# module.net
KiCad netlist of a schematic drawn in EAGLE
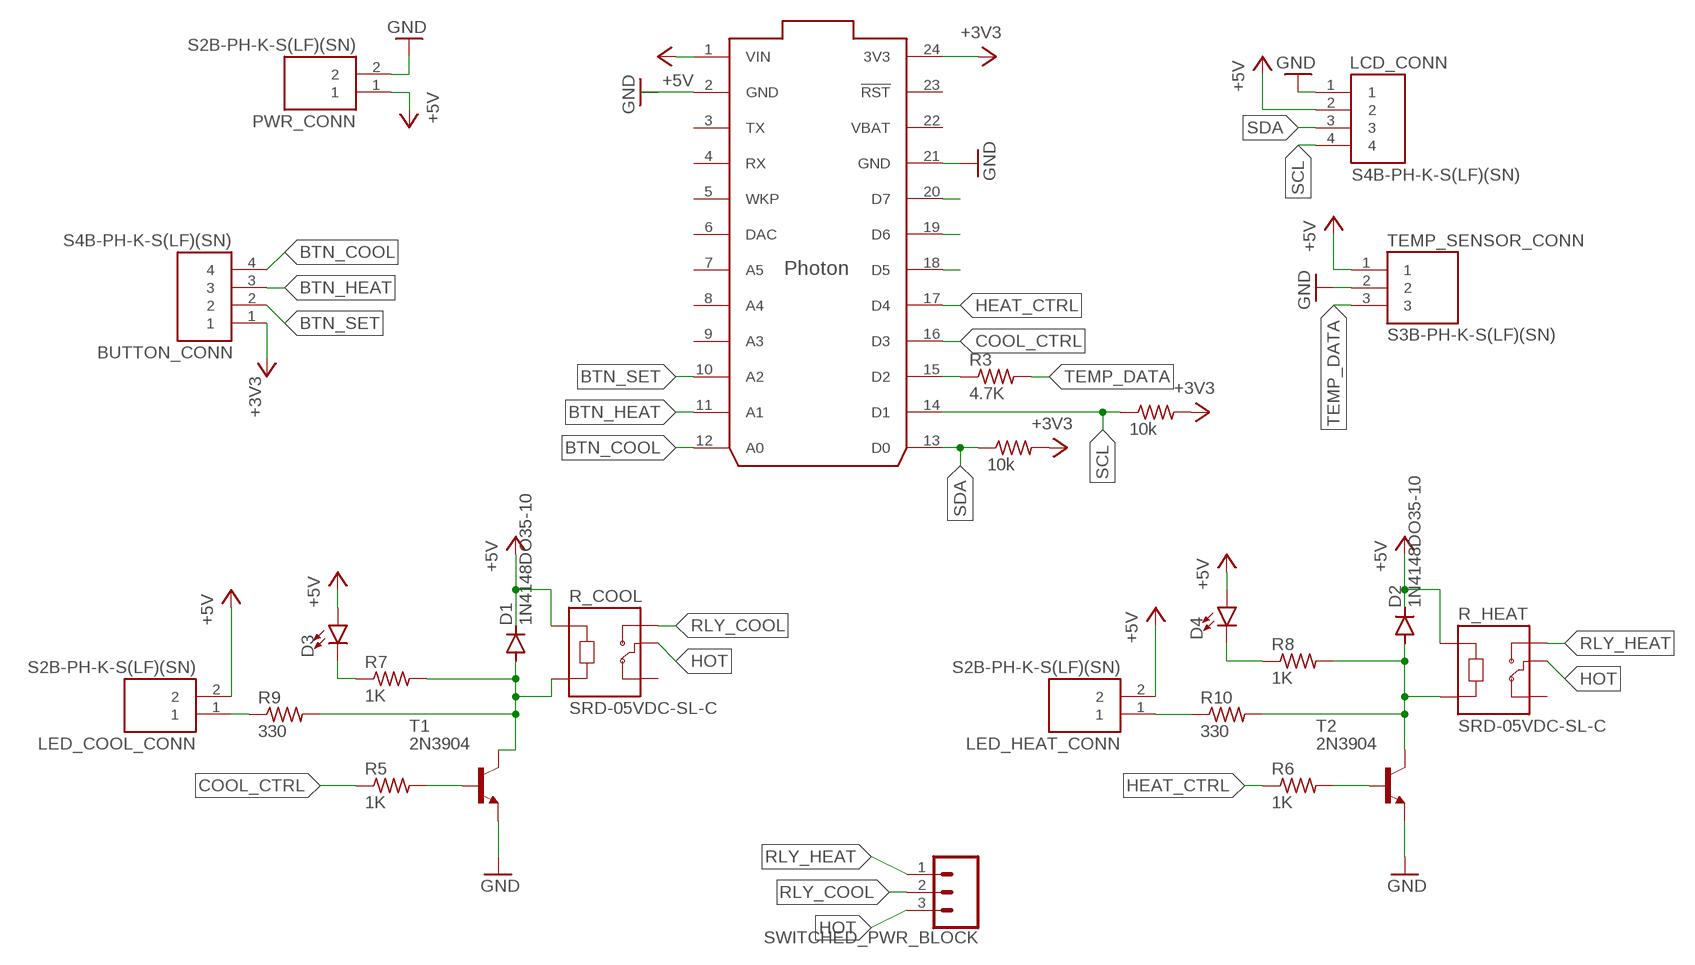
[diagram p0: schematic, sheet 1]

(export (version "E")
  (design (tool "Eeschema 10.0.6"))
  (components
    (comp (ref "BUTTON_CONN")
      (value "S4B-PH-K-S(LF)(SN)")
      (footprint "eagle-import:JST_S4B-PH-K-S(LF)(SN)")
      (fields (field (name "MF") "JST Sales"))
      (libsource (lib "eagle-import") (part "S4B-PH-K-S(LF)(SN)"))
    )
    (comp (ref "D1")
      (value "1N4148DO35-10")
      (footprint "eagle-import:DO35-10")
      (libsource (lib "eagle-import") (part "1N4148DO35-10"))
    )
    (comp (ref "D2")
      (value "1N4148DO35-10")
      (footprint "eagle-import:DO35-10")
      (libsource (lib "eagle-import") (part "1N4148DO35-10"))
    )
    (comp (ref "D3")
      (value "LED5MM")
      (footprint "eagle-import:LED_5MM")
      (libsource (lib "eagle-import") (part "LED5MM"))
    )
    (comp (ref "D4")
      (value "LED5MM")
      (footprint "eagle-import:LED_5MM")
      (libsource (lib "eagle-import") (part "LED5MM"))
    )
    (comp (ref "LCD_CONN")
      (value "S4B-PH-K-S(LF)(SN)")
      (footprint "eagle-import:JST_S4B-PH-K-S(LF)(SN)")
      (fields (field (name "MF") "JST Sales"))
      (libsource (lib "eagle-import") (part "S4B-PH-K-S(LF)(SN)"))
    )
    (comp (ref "LED_COOL_CONN")
      (value "S2B-PH-K-S(LF)(SN)")
      (footprint "eagle-import:JST_S2B-PH-K-S(LF)(SN)")
      (fields (field (name "MF") "JST Sales America Inc."))
      (libsource (lib "eagle-import") (part "S2B-PH-K-S(LF)(SN)"))
    )
    (comp (ref "LED_HEAT_CONN")
      (value "S2B-PH-K-S(LF)(SN)")
      (footprint "eagle-import:JST_S2B-PH-K-S(LF)(SN)")
      (fields (field (name "MF") "JST Sales America Inc."))
      (libsource (lib "eagle-import") (part "S2B-PH-K-S(LF)(SN)"))
    )
    (comp (ref "PWR_CONN")
      (value "S2B-PH-K-S(LF)(SN)")
      (footprint "eagle-import:JST_S2B-PH-K-S(LF)(SN)")
      (fields (field (name "MF") "JST Sales America Inc."))
      (libsource (lib "eagle-import") (part "S2B-PH-K-S(LF)(SN)"))
    )
    (comp (ref "R1")
      (value "10k")
      (footprint "eagle-import:0207_10")
      (libsource (lib "eagle-import") (part "R-US_0207/10"))
    )
    (comp (ref "R2")
      (value "10k")
      (footprint "eagle-import:0207_10")
      (libsource (lib "eagle-import") (part "R-US_0207/10"))
    )
    (comp (ref "R3")
      (value "4.7K")
      (footprint "eagle-import:0207_10")
      (libsource (lib "eagle-import") (part "R-US_0207/10"))
    )
    (comp (ref "R5")
      (value "1K")
      (footprint "eagle-import:0207_10")
      (libsource (lib "eagle-import") (part "R-US_0207/10"))
    )
    (comp (ref "R6")
      (value "1K")
      (footprint "eagle-import:0207_10")
      (libsource (lib "eagle-import") (part "R-US_0207/10"))
    )
    (comp (ref "R7")
      (value "1K")
      (footprint "eagle-import:0207_10")
      (libsource (lib "eagle-import") (part "R-US_0207/10"))
    )
    (comp (ref "R8")
      (value "1K")
      (footprint "eagle-import:0207_10")
      (libsource (lib "eagle-import") (part "R-US_0207/10"))
    )
    (comp (ref "R9")
      (value "330")
      (footprint "eagle-import:0207_10")
      (libsource (lib "eagle-import") (part "R-US_0207/10"))
    )
    (comp (ref "R10")
      (value "330")
      (footprint "eagle-import:0207_10")
      (libsource (lib "eagle-import") (part "R-US_0207/10"))
    )
    (comp (ref "R_COOL")
      (value "SRD-05VDC-SL-C")
      (footprint "eagle-import:RELAY_SRD-05VDC-SL-C")
      (fields (field (name "MF") "Songle Relay"))
      (libsource (lib "eagle-import") (part "SRD-05VDC-SL-C"))
    )
    (comp (ref "R_HEAT")
      (value "SRD-05VDC-SL-C")
      (footprint "eagle-import:RELAY_SRD-05VDC-SL-C")
      (fields (field (name "MF") "Songle Relay"))
      (libsource (lib "eagle-import") (part "SRD-05VDC-SL-C"))
    )
    (comp (ref "SWITCHED_PWR_BLOCK")
      (value "CONN_03-SCREW-5MM")
      (footprint "eagle-import:SCREWTERMINAL-5MM-3")
      (libsource (lib "eagle-import") (part "CONN_03-SCREW-5MM"))
    )
    (comp (ref "T1")
      (value "2N3904")
      (footprint "eagle-import:TO92")
      (libsource (lib "eagle-import") (part "2N3904"))
    )
    (comp (ref "T2")
      (value "2N3904")
      (footprint "eagle-import:TO92")
      (libsource (lib "eagle-import") (part "2N3904"))
    )
    (comp (ref "TEMP_SENSOR_CONN")
      (value "S3B-PH-K-S(LF)(SN)")
      (footprint "eagle-import:JST_S3B-PH-K-S(LF)(SN)")
      (fields (field (name "DIGI-KEY_PART_NUMBER") "455-1720-ND") (field (name "MF") "JST Sales"))
      (libsource (lib "eagle-import") (part "S3B-PH-K-S(LF)(SN)"))
    )
    (comp (ref "U$1")
      (value "PHOTON_WITH_HEADERS")
      (footprint "eagle-import:PHOTON")
      (libsource (lib "eagle-import") (part "PHOTON_WITH_HEADERS"))
    )
  )
  (nets
    (net (code "1") (name "+3V3") (class "Default")
      (node (ref "BUTTON_CONN") (pin "1") (pinfunction "1_1") (pintype "passive"))
      (node (ref "R1") (pin "2") (pinfunction "2_2") (pintype "passive"))
      (node (ref "R2") (pin "2") (pinfunction "2_2") (pintype "passive"))
      (node (ref "U$1") (pin "24") (pinfunction "3V3_24") (pintype "power_in"))
    )
    (net (code "2") (name "+5V") (class "Default")
      (node (ref "D1") (pin "C") (pinfunction "C_C") (pintype "passive"))
      (node (ref "D2") (pin "C") (pinfunction "C_C") (pintype "passive"))
      (node (ref "D3") (pin "A") (pinfunction "A_A") (pintype "passive"))
      (node (ref "D4") (pin "A") (pinfunction "A_A") (pintype "passive"))
      (node (ref "LCD_CONN") (pin "2") (pinfunction "2_2") (pintype "passive"))
      (node (ref "LED_COOL_CONN") (pin "2") (pinfunction "2_2") (pintype "passive"))
      (node (ref "LED_HEAT_CONN") (pin "2") (pinfunction "2_2") (pintype "passive"))
      (node (ref "PWR_CONN") (pin "1") (pinfunction "1_1") (pintype "passive"))
      (node (ref "R_COOL") (pin "A1") (pinfunction "A1_A1") (pintype "passive"))
      (node (ref "R_HEAT") (pin "A1") (pinfunction "A1_A1") (pintype "passive"))
      (node (ref "TEMP_SENSOR_CONN") (pin "1") (pinfunction "1_1") (pintype "passive"))
      (node (ref "U$1") (pin "1") (pinfunction "VIN_1") (pintype "power_in"))
    )
    (net (code "3") (name "/VBAT") (class "Default")
      (node (ref "U$1") (pin "22") (pinfunction "VBAT_22") (pintype "power_in"))
    )
    (net (code "4") (name "BTN_COOL") (class "Default")
      (node (ref "BUTTON_CONN") (pin "4") (pinfunction "4_4") (pintype "passive"))
      (node (ref "U$1") (pin "12") (pinfunction "A0_12") (pintype "bidirectional"))
    )
    (net (code "5") (name "BTN_HEAT") (class "Default")
      (node (ref "BUTTON_CONN") (pin "3") (pinfunction "3_3") (pintype "passive"))
      (node (ref "U$1") (pin "11") (pinfunction "A1_11") (pintype "bidirectional"))
    )
    (net (code "6") (name "BTN_SET") (class "Default")
      (node (ref "BUTTON_CONN") (pin "2") (pinfunction "2_2") (pintype "passive"))
      (node (ref "U$1") (pin "10") (pinfunction "A2_10") (pintype "bidirectional"))
      (node (ref "U$1") (pin "20") (pinfunction "D7_20") (pintype "bidirectional"))
    )
    (net (code "7") (name "COOL_CTRL") (class "Default")
      (node (ref "R5") (pin "1") (pinfunction "1_1") (pintype "passive"))
      (node (ref "U$1") (pin "16") (pinfunction "D3_16") (pintype "bidirectional"))
    )
    (net (code "8") (name "GND") (class "Default")
      (node (ref "LCD_CONN") (pin "1") (pinfunction "1_1") (pintype "passive"))
      (node (ref "PWR_CONN") (pin "2") (pinfunction "2_2") (pintype "passive"))
      (node (ref "T1") (pin "3") (pinfunction "E_3") (pintype "passive"))
      (node (ref "T2") (pin "3") (pinfunction "E_3") (pintype "passive"))
      (node (ref "TEMP_SENSOR_CONN") (pin "2") (pinfunction "2_2") (pintype "passive"))
      (node (ref "U$1") (pin "2") (pinfunction "GND_2") (pintype "power_in"))
      (node (ref "U$1") (pin "21") (pinfunction "GND_21") (pintype "power_in"))
    )
    (net (code "9") (name "HEAT_CTRL") (class "Default")
      (node (ref "R6") (pin "1") (pinfunction "1_1") (pintype "passive"))
      (node (ref "U$1") (pin "17") (pinfunction "D4_17") (pintype "bidirectional"))
    )
    (net (code "10") (name "HOT") (class "Default")
      (node (ref "R_COOL") (pin "COM") (pinfunction "COM_COM") (pintype "passive"))
      (node (ref "R_HEAT") (pin "COM") (pinfunction "COM_COM") (pintype "passive"))
      (node (ref "SWITCHED_PWR_BLOCK") (pin "3") (pinfunction "3_3") (pintype "passive"))
    )
    (net (code "11") (name "Net-(D3-C)") (class "Default")
      (node (ref "D3") (pin "K") (pinfunction "C_K") (pintype "passive"))
      (node (ref "R7") (pin "1") (pinfunction "1_1") (pintype "passive"))
    )
    (net (code "12") (name "Net-(D4-C)") (class "Default")
      (node (ref "D4") (pin "K") (pinfunction "C_K") (pintype "passive"))
      (node (ref "R8") (pin "1") (pinfunction "1_1") (pintype "passive"))
    )
    (net (code "13") (name "Net-(LED_COOL_CONN-Pad1)") (class "Default")
      (node (ref "LED_COOL_CONN") (pin "1") (pinfunction "1_1") (pintype "passive"))
      (node (ref "R9") (pin "1") (pinfunction "1_1") (pintype "passive"))
    )
    (net (code "14") (name "Net-(LED_HEAT_CONN-Pad1)") (class "Default")
      (node (ref "LED_HEAT_CONN") (pin "1") (pinfunction "1_1") (pintype "passive"))
      (node (ref "R10") (pin "1") (pinfunction "1_1") (pintype "passive"))
    )
    (net (code "15") (name "Net-(T1-B)") (class "Default")
      (node (ref "R5") (pin "2") (pinfunction "2_2") (pintype "passive"))
      (node (ref "T1") (pin "2") (pinfunction "B_2") (pintype "passive"))
    )
    (net (code "16") (name "Net-(T1-C)") (class "Default")
      (node (ref "D1") (pin "A") (pinfunction "A_A") (pintype "passive"))
      (node (ref "R7") (pin "2") (pinfunction "2_2") (pintype "passive"))
      (node (ref "R9") (pin "2") (pinfunction "2_2") (pintype "passive"))
      (node (ref "R_COOL") (pin "A2") (pinfunction "A2_A2") (pintype "passive"))
      (node (ref "T1") (pin "1") (pinfunction "C_1") (pintype "passive"))
    )
    (net (code "17") (name "Net-(T2-B)") (class "Default")
      (node (ref "R6") (pin "2") (pinfunction "2_2") (pintype "passive"))
      (node (ref "T2") (pin "2") (pinfunction "B_2") (pintype "passive"))
    )
    (net (code "18") (name "Net-(T2-C)") (class "Default")
      (node (ref "D2") (pin "A") (pinfunction "A_A") (pintype "passive"))
      (node (ref "R10") (pin "2") (pinfunction "2_2") (pintype "passive"))
      (node (ref "R8") (pin "2") (pinfunction "2_2") (pintype "passive"))
      (node (ref "R_HEAT") (pin "A2") (pinfunction "A2_A2") (pintype "passive"))
      (node (ref "T2") (pin "1") (pinfunction "C_1") (pintype "passive"))
    )
    (net (code "19") (name "Net-(U$1-D2)") (class "Default")
      (node (ref "R3") (pin "1") (pinfunction "1_1") (pintype "passive"))
      (node (ref "U$1") (pin "15") (pinfunction "D2_15") (pintype "bidirectional"))
    )
    (net (code "20") (name "RLY_COOL") (class "Default")
      (node (ref "R_COOL") (pin "NO") (pinfunction "NO_NO") (pintype "passive"))
      (node (ref "SWITCHED_PWR_BLOCK") (pin "2") (pinfunction "2_2") (pintype "passive"))
    )
    (net (code "21") (name "RLY_HEAT") (class "Default")
      (node (ref "R_HEAT") (pin "NO") (pinfunction "NO_NO") (pintype "passive"))
      (node (ref "SWITCHED_PWR_BLOCK") (pin "1") (pinfunction "1_1") (pintype "passive"))
    )
    (net (code "22") (name "SCL") (class "Default")
      (node (ref "LCD_CONN") (pin "4") (pinfunction "4_4") (pintype "passive"))
      (node (ref "R1") (pin "1") (pinfunction "1_1") (pintype "passive"))
      (node (ref "U$1") (pin "14") (pinfunction "D1_14") (pintype "bidirectional"))
    )
    (net (code "23") (name "SDA") (class "Default")
      (node (ref "LCD_CONN") (pin "3") (pinfunction "3_3") (pintype "passive"))
      (node (ref "R2") (pin "1") (pinfunction "1_1") (pintype "passive"))
      (node (ref "U$1") (pin "13") (pinfunction "D0_13") (pintype "bidirectional"))
    )
    (net (code "24") (name "TEMP_DATA") (class "Default")
      (node (ref "R3") (pin "2") (pinfunction "2_2") (pintype "passive"))
      (node (ref "TEMP_SENSOR_CONN") (pin "3") (pinfunction "3_3") (pintype "passive"))
    )
    (net (code "25") (name "unconnected-(R_COOL-PadNC)") (class "Default")
      (node (ref "R_COOL") (pin "NC") (pinfunction "NC_NC") (pintype "passive"))
    )
    (net (code "26") (name "unconnected-(R_HEAT-PadNC)") (class "Default")
      (node (ref "R_HEAT") (pin "NC") (pinfunction "NC_NC") (pintype "passive"))
    )
    (net (code "27") (name "unconnected-(U$1-A3-Pad9)") (class "Default")
      (node (ref "U$1") (pin "9") (pinfunction "A3_9") (pintype "bidirectional"))
    )
    (net (code "28") (name "unconnected-(U$1-A4-Pad8)") (class "Default")
      (node (ref "U$1") (pin "8") (pinfunction "A4_8") (pintype "bidirectional"))
    )
    (net (code "29") (name "unconnected-(U$1-A5-Pad7)") (class "Default")
      (node (ref "U$1") (pin "7") (pinfunction "A5_7") (pintype "bidirectional"))
    )
    (net (code "30") (name "unconnected-(U$1-D5-Pad18)") (class "Default")
      (node (ref "U$1") (pin "18") (pinfunction "D5_18") (pintype "bidirectional"))
    )
    (net (code "31") (name "unconnected-(U$1-D6-Pad19)") (class "Default")
      (node (ref "U$1") (pin "19") (pinfunction "D6_19") (pintype "bidirectional"))
    )
    (net (code "32") (name "unconnected-(U$1-DAC-Pad6)") (class "Default")
      (node (ref "U$1") (pin "6") (pinfunction "DAC_6") (pintype "bidirectional"))
    )
    (net (code "33") (name "unconnected-(U$1-RX-Pad4)") (class "Default")
      (node (ref "U$1") (pin "4") (pinfunction "RX_4") (pintype "bidirectional"))
    )
    (net (code "34") (name "unconnected-(U$1-TX-Pad3)") (class "Default")
      (node (ref "U$1") (pin "3") (pinfunction "TX_3") (pintype "bidirectional"))
    )
    (net (code "35") (name "unconnected-(U$1-WKP-Pad5)") (class "Default")
      (node (ref "U$1") (pin "5") (pinfunction "WKP_5") (pintype "bidirectional"))
    )
    (net (code "36") (name "unconnected-(U$1-~{RST}-Pad23)") (class "Default")
      (node (ref "U$1") (pin "23") (pinfunction "~{RST}_23") (pintype "bidirectional"))
    )
  )
)
